# 8x8_LED_Cathode_Base_V5.net
KiCad netlist of a schematic drawn in EAGLE
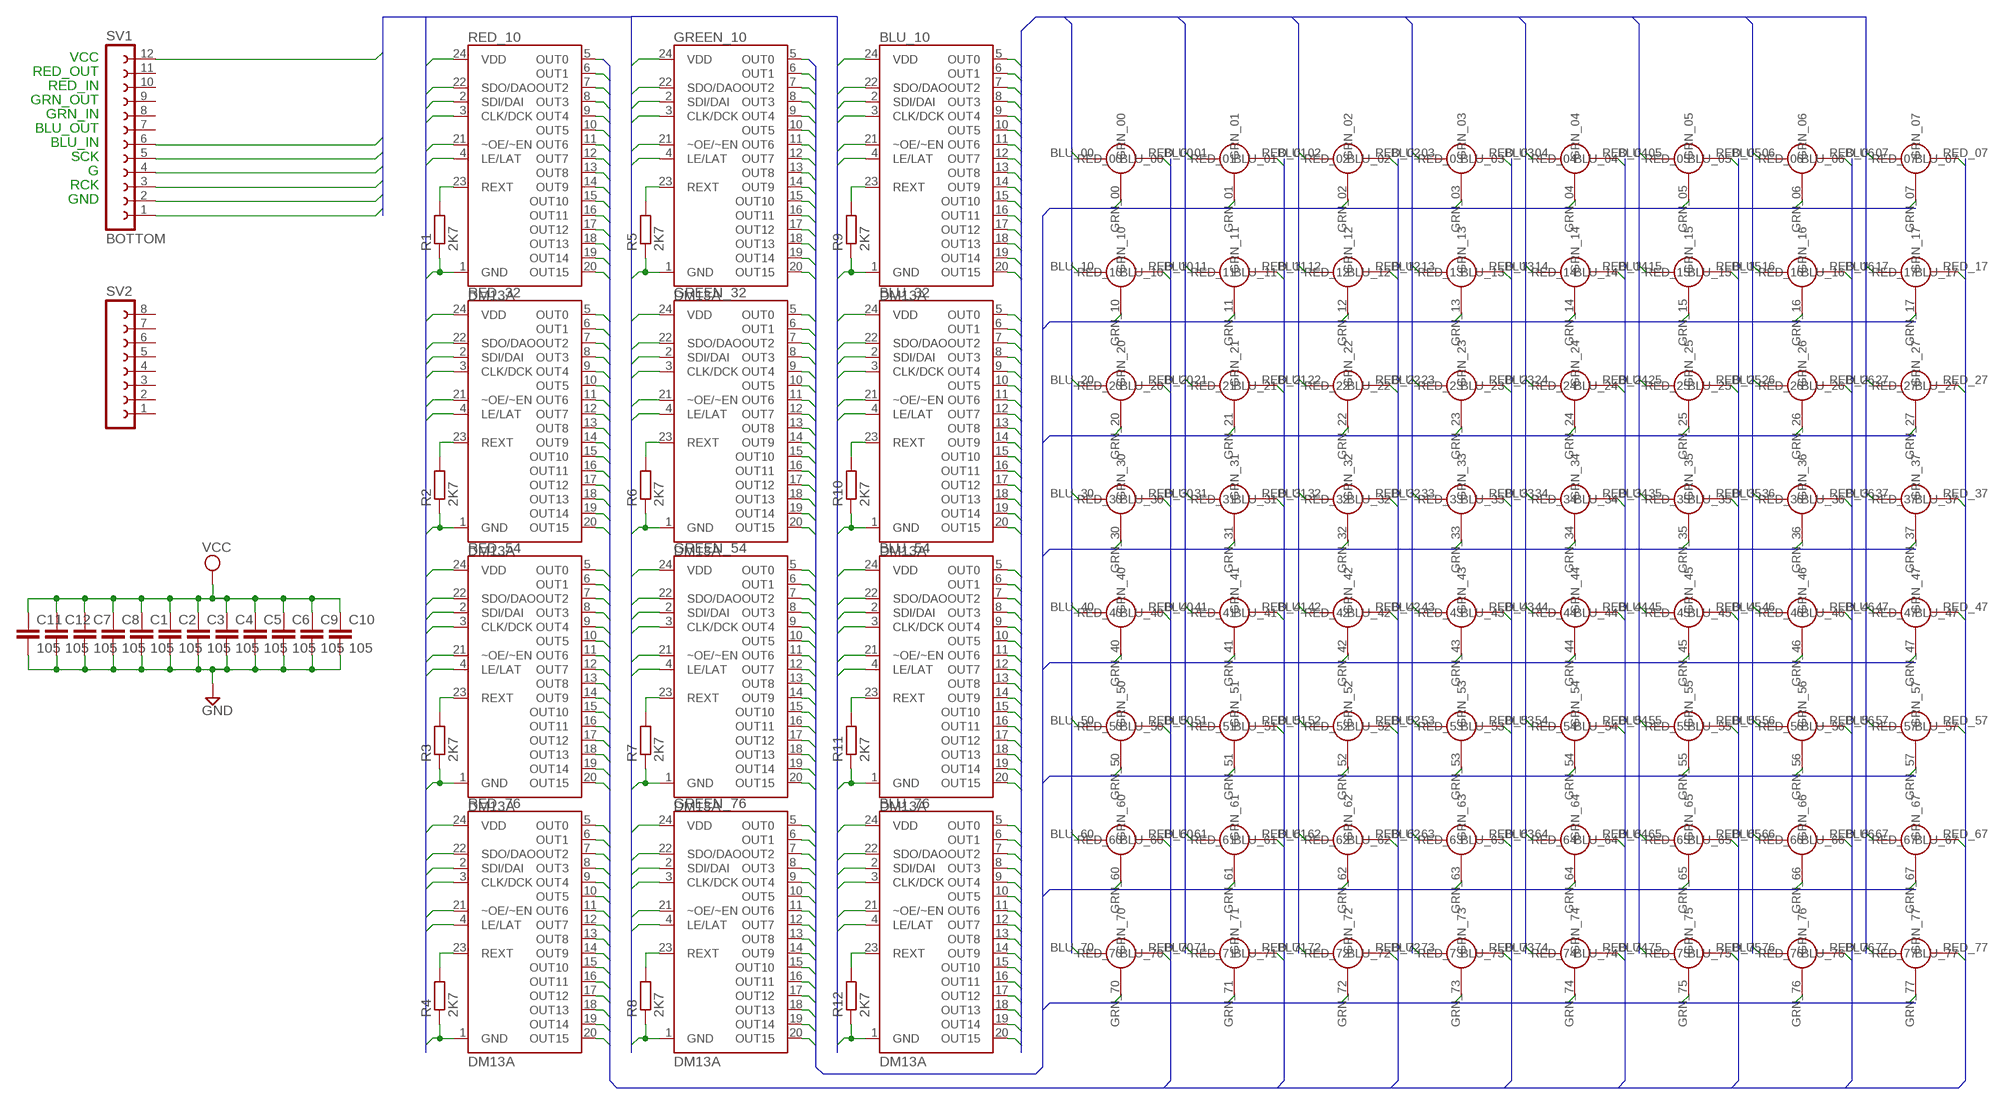
[diagram p0: schematic, sheet 1]

(export (version "E")
  (design (tool "Eeschema 10.0.6"))
  (components
    (comp (ref "BLU_10")
      (value "DM13A")
      (footprint "eagle-import:DIL24-3")
      (libsource (lib "eagle-import") (part "DM13A"))
    )
    (comp (ref "BLU_32")
      (value "DM13A")
      (footprint "eagle-import:DIL24-3")
      (libsource (lib "eagle-import") (part "DM13A"))
    )
    (comp (ref "BLU_54")
      (value "DM13A")
      (footprint "eagle-import:DIL24-3")
      (libsource (lib "eagle-import") (part "DM13A"))
    )
    (comp (ref "BLU_76")
      (value "DM13A")
      (footprint "eagle-import:DIL24-3")
      (libsource (lib "eagle-import") (part "DM13A"))
    )
    (comp (ref "C1")
      (value "105")
      (footprint "eagle-import:C1206")
      (libsource (lib "eagle-import") (part "C-EUC1206"))
    )
    (comp (ref "C2")
      (value "105")
      (footprint "eagle-import:C1206")
      (libsource (lib "eagle-import") (part "C-EUC1206"))
    )
    (comp (ref "C3")
      (value "105")
      (footprint "eagle-import:C1206")
      (libsource (lib "eagle-import") (part "C-EUC1206"))
    )
    (comp (ref "C4")
      (value "105")
      (footprint "eagle-import:C1206")
      (libsource (lib "eagle-import") (part "C-EUC1206"))
    )
    (comp (ref "C5")
      (value "105")
      (footprint "eagle-import:C1206")
      (libsource (lib "eagle-import") (part "C-EUC1206"))
    )
    (comp (ref "C6")
      (value "105")
      (footprint "eagle-import:C1206")
      (libsource (lib "eagle-import") (part "C-EUC1206"))
    )
    (comp (ref "C7")
      (value "105")
      (footprint "eagle-import:C1206")
      (libsource (lib "eagle-import") (part "C-EUC1206"))
    )
    (comp (ref "C8")
      (value "105")
      (footprint "eagle-import:C1206")
      (libsource (lib "eagle-import") (part "C-EUC1206"))
    )
    (comp (ref "C9")
      (value "105")
      (footprint "eagle-import:C1206")
      (libsource (lib "eagle-import") (part "C-EUC1206"))
    )
    (comp (ref "C10")
      (value "105")
      (footprint "eagle-import:C1206")
      (libsource (lib "eagle-import") (part "C-EUC1206"))
    )
    (comp (ref "C11")
      (value "105")
      (footprint "eagle-import:C1206")
      (libsource (lib "eagle-import") (part "C-EUC1206"))
    )
    (comp (ref "C12")
      (value "105")
      (footprint "eagle-import:C1206")
      (libsource (lib "eagle-import") (part "C-EUC1206"))
    )
    (comp (ref "GREEN_10")
      (value "DM13A")
      (footprint "eagle-import:DIL24-3")
      (libsource (lib "eagle-import") (part "DM13A"))
    )
    (comp (ref "GREEN_32")
      (value "DM13A")
      (footprint "eagle-import:DIL24-3")
      (libsource (lib "eagle-import") (part "DM13A"))
    )
    (comp (ref "GREEN_54")
      (value "DM13A")
      (footprint "eagle-import:DIL24-3")
      (libsource (lib "eagle-import") (part "DM13A"))
    )
    (comp (ref "GREEN_76")
      (value "DM13A")
      (footprint "eagle-import:DIL24-3")
      (libsource (lib "eagle-import") (part "DM13A"))
    )
    (comp (ref "R1")
      (value "2K7")
      (footprint "eagle-import:R1206")
      (libsource (lib "eagle-import") (part "R-EU_R1206"))
    )
    (comp (ref "R2")
      (value "2K7")
      (footprint "eagle-import:R1206")
      (libsource (lib "eagle-import") (part "R-EU_R1206"))
    )
    (comp (ref "R3")
      (value "2K7")
      (footprint "eagle-import:R1206")
      (libsource (lib "eagle-import") (part "R-EU_R1206"))
    )
    (comp (ref "R4")
      (value "2K7")
      (footprint "eagle-import:R1206")
      (libsource (lib "eagle-import") (part "R-EU_R1206"))
    )
    (comp (ref "R5")
      (value "2K7")
      (footprint "eagle-import:R1206")
      (libsource (lib "eagle-import") (part "R-EU_R1206"))
    )
    (comp (ref "R6")
      (value "2K7")
      (footprint "eagle-import:R1206")
      (libsource (lib "eagle-import") (part "R-EU_R1206"))
    )
    (comp (ref "R7")
      (value "2K7")
      (footprint "eagle-import:R1206")
      (libsource (lib "eagle-import") (part "R-EU_R1206"))
    )
    (comp (ref "R8")
      (value "2K7")
      (footprint "eagle-import:R1206")
      (libsource (lib "eagle-import") (part "R-EU_R1206"))
    )
    (comp (ref "R9")
      (value "2K7")
      (footprint "eagle-import:R1206")
      (libsource (lib "eagle-import") (part "R-EU_R1206"))
    )
    (comp (ref "R10")
      (value "2K7")
      (footprint "eagle-import:R1206")
      (libsource (lib "eagle-import") (part "R-EU_R1206"))
    )
    (comp (ref "R11")
      (value "2K7")
      (footprint "eagle-import:R1206")
      (libsource (lib "eagle-import") (part "R-EU_R1206"))
    )
    (comp (ref "R12")
      (value "2K7")
      (footprint "eagle-import:R1206")
      (libsource (lib "eagle-import") (part "R-EU_R1206"))
    )
    (comp (ref "RED_10")
      (value "DM13A")
      (footprint "eagle-import:DIL24-3")
      (libsource (lib "eagle-import") (part "DM13A"))
    )
    (comp (ref "RED_32")
      (value "DM13A")
      (footprint "eagle-import:DIL24-3")
      (libsource (lib "eagle-import") (part "DM13A"))
    )
    (comp (ref "RED_54")
      (value "DM13A")
      (footprint "eagle-import:DIL24-3")
      (libsource (lib "eagle-import") (part "DM13A"))
    )
    (comp (ref "RED_76")
      (value "DM13A")
      (footprint "eagle-import:DIL24-3")
      (libsource (lib "eagle-import") (part "DM13A"))
    )
    (comp (ref "SV1")
      (value "BOTTOM")
      (footprint "eagle-import:FE12")
      (libsource (lib "eagle-import") (part "FE12-1"))
    )
    (comp (ref "SV2")
      (value "FE08-1")
      (footprint "eagle-import:FE08")
      (libsource (lib "eagle-import") (part "FE08-1"))
    )
    (comp (ref "U$1")
      (value "8X8_RGB_COLUMN")
      (footprint "eagle-import:8X8_RGB_LED_120")
      (libsource (lib "eagle-import") (part "8X8_RGB_COLUMN"))
    )
  )
  (nets
    (net (code "2") (name "/BLANK") (class "Default")
      (node (ref "BLU_10") (pin "21") (pinfunction "~{OE/}EN_21") (pintype "bidirectional"))
      (node (ref "BLU_32") (pin "21") (pinfunction "~{OE/}EN_21") (pintype "bidirectional"))
      (node (ref "BLU_54") (pin "21") (pinfunction "~{OE/}EN_21") (pintype "bidirectional"))
      (node (ref "BLU_76") (pin "21") (pinfunction "~{OE/}EN_21") (pintype "bidirectional"))
      (node (ref "GREEN_10") (pin "21") (pinfunction "~{OE/}EN_21") (pintype "bidirectional"))
      (node (ref "GREEN_32") (pin "21") (pinfunction "~{OE/}EN_21") (pintype "bidirectional"))
      (node (ref "GREEN_54") (pin "21") (pinfunction "~{OE/}EN_21") (pintype "bidirectional"))
      (node (ref "GREEN_76") (pin "21") (pinfunction "~{OE/}EN_21") (pintype "bidirectional"))
      (node (ref "RED_10") (pin "21") (pinfunction "~{OE/}EN_21") (pintype "bidirectional"))
      (node (ref "RED_32") (pin "21") (pinfunction "~{OE/}EN_21") (pintype "bidirectional"))
      (node (ref "RED_54") (pin "21") (pinfunction "~{OE/}EN_21") (pintype "bidirectional"))
      (node (ref "RED_76") (pin "21") (pinfunction "~{OE/}EN_21") (pintype "bidirectional"))
      (node (ref "SV1") (pin "4") (pinfunction "4_4") (pintype "passive"))
    )
    (net (code "3") (name "/BLU_00") (class "Default")
      (node (ref "BLU_10") (pin "5") (pinfunction "OUT0_5") (pintype "bidirectional"))
      (node (ref "U$1") (pin "BLU_00") (pinfunction "BLU_00_BLU_00") (pintype "bidirectional"))
    )
    (net (code "4") (name "/BLU_01") (class "Default")
      (node (ref "BLU_10") (pin "6") (pinfunction "OUT1_6") (pintype "bidirectional"))
      (node (ref "U$1") (pin "BLU_01") (pinfunction "BLU_01_BLU_01") (pintype "bidirectional"))
    )
    (net (code "5") (name "/BLU_02") (class "Default")
      (node (ref "BLU_10") (pin "7") (pinfunction "OUT2_7") (pintype "bidirectional"))
      (node (ref "U$1") (pin "BLU_02") (pinfunction "BLU_02_BLU_02") (pintype "bidirectional"))
    )
    (net (code "6") (name "/BLU_03") (class "Default")
      (node (ref "BLU_10") (pin "8") (pinfunction "OUT3_8") (pintype "bidirectional"))
      (node (ref "U$1") (pin "BLU_03") (pinfunction "BLU_03_BLU_03") (pintype "bidirectional"))
    )
    (net (code "7") (name "/BLU_04") (class "Default")
      (node (ref "BLU_10") (pin "9") (pinfunction "OUT4_9") (pintype "bidirectional"))
      (node (ref "U$1") (pin "BLU_04") (pinfunction "BLU_04_BLU_04") (pintype "bidirectional"))
    )
    (net (code "8") (name "/BLU_05") (class "Default")
      (node (ref "BLU_10") (pin "10") (pinfunction "OUT5_10") (pintype "bidirectional"))
      (node (ref "U$1") (pin "BLU_05") (pinfunction "BLU_05_BLU_05") (pintype "bidirectional"))
    )
    (net (code "9") (name "/BLU_06") (class "Default")
      (node (ref "BLU_10") (pin "11") (pinfunction "OUT6_11") (pintype "bidirectional"))
      (node (ref "U$1") (pin "BLU_06") (pinfunction "BLU_06_BLU_06") (pintype "bidirectional"))
    )
    (net (code "10") (name "/BLU_07") (class "Default")
      (node (ref "BLU_10") (pin "12") (pinfunction "OUT7_12") (pintype "bidirectional"))
      (node (ref "U$1") (pin "BLU_07") (pinfunction "BLU_07_BLU_07") (pintype "bidirectional"))
    )
    (net (code "11") (name "/BLU_10") (class "Default")
      (node (ref "BLU_10") (pin "13") (pinfunction "OUT8_13") (pintype "bidirectional"))
      (node (ref "U$1") (pin "BLU_10") (pinfunction "BLU_10_BLU_10") (pintype "bidirectional"))
    )
    (net (code "12") (name "/BLU_11") (class "Default")
      (node (ref "BLU_10") (pin "14") (pinfunction "OUT9_14") (pintype "bidirectional"))
      (node (ref "U$1") (pin "BLU_11") (pinfunction "BLU_11_BLU_11") (pintype "bidirectional"))
    )
    (net (code "13") (name "/BLU_12") (class "Default")
      (node (ref "BLU_10") (pin "15") (pinfunction "OUT10_15") (pintype "bidirectional"))
      (node (ref "U$1") (pin "BLU_12") (pinfunction "BLU_12_BLU_12") (pintype "bidirectional"))
    )
    (net (code "14") (name "/BLU_13") (class "Default")
      (node (ref "BLU_10") (pin "16") (pinfunction "OUT11_16") (pintype "bidirectional"))
      (node (ref "U$1") (pin "BLU_13") (pinfunction "BLU_13_BLU_13") (pintype "bidirectional"))
    )
    (net (code "15") (name "/BLU_14") (class "Default")
      (node (ref "BLU_10") (pin "17") (pinfunction "OUT12_17") (pintype "bidirectional"))
      (node (ref "U$1") (pin "BLU_14") (pinfunction "BLU_14_BLU_14") (pintype "bidirectional"))
    )
    (net (code "16") (name "/BLU_15") (class "Default")
      (node (ref "BLU_10") (pin "18") (pinfunction "OUT13_18") (pintype "bidirectional"))
      (node (ref "U$1") (pin "BLU_15") (pinfunction "BLU_15_BLU_15") (pintype "bidirectional"))
    )
    (net (code "17") (name "/BLU_16") (class "Default")
      (node (ref "BLU_10") (pin "19") (pinfunction "OUT14_19") (pintype "bidirectional"))
      (node (ref "U$1") (pin "BLU_16") (pinfunction "BLU_16_BLU_16") (pintype "bidirectional"))
    )
    (net (code "18") (name "/BLU_17") (class "Default")
      (node (ref "BLU_10") (pin "20") (pinfunction "OUT15_20") (pintype "bidirectional"))
      (node (ref "U$1") (pin "BLU_17") (pinfunction "BLU_17_BLU_17") (pintype "bidirectional"))
    )
    (net (code "19") (name "/BLU_20") (class "Default")
      (node (ref "BLU_32") (pin "5") (pinfunction "OUT0_5") (pintype "bidirectional"))
      (node (ref "U$1") (pin "BLU_20") (pinfunction "BLU_20_BLU_20") (pintype "bidirectional"))
    )
    (net (code "20") (name "/BLU_21") (class "Default")
      (node (ref "BLU_32") (pin "6") (pinfunction "OUT1_6") (pintype "bidirectional"))
      (node (ref "U$1") (pin "BLU_21") (pinfunction "BLU_21_BLU_21") (pintype "bidirectional"))
    )
    (net (code "21") (name "/BLU_22") (class "Default")
      (node (ref "BLU_32") (pin "7") (pinfunction "OUT2_7") (pintype "bidirectional"))
      (node (ref "U$1") (pin "BLU_22") (pinfunction "BLU_22_BLU_22") (pintype "bidirectional"))
    )
    (net (code "22") (name "/BLU_23") (class "Default")
      (node (ref "BLU_32") (pin "8") (pinfunction "OUT3_8") (pintype "bidirectional"))
      (node (ref "U$1") (pin "BLU_23") (pinfunction "BLU_23_BLU_23") (pintype "bidirectional"))
    )
    (net (code "23") (name "/BLU_24") (class "Default")
      (node (ref "BLU_32") (pin "9") (pinfunction "OUT4_9") (pintype "bidirectional"))
      (node (ref "U$1") (pin "BLU_24") (pinfunction "BLU_24_BLU_24") (pintype "bidirectional"))
    )
    (net (code "24") (name "/BLU_25") (class "Default")
      (node (ref "BLU_32") (pin "10") (pinfunction "OUT5_10") (pintype "bidirectional"))
      (node (ref "U$1") (pin "BLU_25") (pinfunction "BLU_25_BLU_25") (pintype "bidirectional"))
    )
    (net (code "25") (name "/BLU_26") (class "Default")
      (node (ref "BLU_32") (pin "11") (pinfunction "OUT6_11") (pintype "bidirectional"))
      (node (ref "U$1") (pin "BLU_26") (pinfunction "BLU_26_BLU_26") (pintype "bidirectional"))
    )
    (net (code "26") (name "/BLU_27") (class "Default")
      (node (ref "BLU_32") (pin "12") (pinfunction "OUT7_12") (pintype "bidirectional"))
      (node (ref "U$1") (pin "BLU_27") (pinfunction "BLU_27_BLU_27") (pintype "bidirectional"))
    )
    (net (code "27") (name "/BLU_30") (class "Default")
      (node (ref "BLU_32") (pin "13") (pinfunction "OUT8_13") (pintype "bidirectional"))
      (node (ref "U$1") (pin "BLU_30") (pinfunction "BLU_30_BLU_30") (pintype "bidirectional"))
    )
    (net (code "28") (name "/BLU_31") (class "Default")
      (node (ref "BLU_32") (pin "14") (pinfunction "OUT9_14") (pintype "bidirectional"))
      (node (ref "U$1") (pin "BLU_31") (pinfunction "BLU_31_BLU_31") (pintype "bidirectional"))
    )
    (net (code "29") (name "/BLU_32") (class "Default")
      (node (ref "BLU_32") (pin "15") (pinfunction "OUT10_15") (pintype "bidirectional"))
      (node (ref "U$1") (pin "BLU_32") (pinfunction "BLU_32_BLU_32") (pintype "bidirectional"))
    )
    (net (code "30") (name "/BLU_32_DATA") (class "Default")
      (node (ref "BLU_10") (pin "22") (pinfunction "SDO/DAO_22") (pintype "bidirectional"))
      (node (ref "BLU_32") (pin "2") (pinfunction "SDI/DAI_2") (pintype "bidirectional"))
    )
    (net (code "31") (name "/BLU_33") (class "Default")
      (node (ref "BLU_32") (pin "16") (pinfunction "OUT11_16") (pintype "bidirectional"))
      (node (ref "U$1") (pin "BLU_33") (pinfunction "BLU_33_BLU_33") (pintype "bidirectional"))
    )
    (net (code "32") (name "/BLU_34") (class "Default")
      (node (ref "BLU_32") (pin "17") (pinfunction "OUT12_17") (pintype "bidirectional"))
      (node (ref "U$1") (pin "BLU_34") (pinfunction "BLU_34_BLU_34") (pintype "bidirectional"))
    )
    (net (code "33") (name "/BLU_35") (class "Default")
      (node (ref "BLU_32") (pin "18") (pinfunction "OUT13_18") (pintype "bidirectional"))
      (node (ref "U$1") (pin "BLU_35") (pinfunction "BLU_35_BLU_35") (pintype "bidirectional"))
    )
    (net (code "34") (name "/BLU_36") (class "Default")
      (node (ref "BLU_32") (pin "19") (pinfunction "OUT14_19") (pintype "bidirectional"))
      (node (ref "U$1") (pin "BLU_36") (pinfunction "BLU_36_BLU_36") (pintype "bidirectional"))
    )
    (net (code "35") (name "/BLU_37") (class "Default")
      (node (ref "BLU_32") (pin "20") (pinfunction "OUT15_20") (pintype "bidirectional"))
      (node (ref "U$1") (pin "BLU_37") (pinfunction "BLU_37_BLU_37") (pintype "bidirectional"))
    )
    (net (code "36") (name "/BLU_40") (class "Default")
      (node (ref "BLU_54") (pin "5") (pinfunction "OUT0_5") (pintype "bidirectional"))
      (node (ref "U$1") (pin "BLU_40") (pinfunction "BLU_40_BLU_40") (pintype "bidirectional"))
    )
    (net (code "37") (name "/BLU_41") (class "Default")
      (node (ref "BLU_54") (pin "6") (pinfunction "OUT1_6") (pintype "bidirectional"))
      (node (ref "U$1") (pin "BLU_41") (pinfunction "BLU_41_BLU_41") (pintype "bidirectional"))
    )
    (net (code "38") (name "/BLU_42") (class "Default")
      (node (ref "BLU_54") (pin "7") (pinfunction "OUT2_7") (pintype "bidirectional"))
      (node (ref "U$1") (pin "BLU_42") (pinfunction "BLU_42_BLU_42") (pintype "bidirectional"))
    )
    (net (code "39") (name "/BLU_43") (class "Default")
      (node (ref "BLU_54") (pin "8") (pinfunction "OUT3_8") (pintype "bidirectional"))
      (node (ref "U$1") (pin "BLU_43") (pinfunction "BLU_43_BLU_43") (pintype "bidirectional"))
    )
    (net (code "40") (name "/BLU_44") (class "Default")
      (node (ref "BLU_54") (pin "9") (pinfunction "OUT4_9") (pintype "bidirectional"))
      (node (ref "U$1") (pin "BLU_44") (pinfunction "BLU_44_BLU_44") (pintype "bidirectional"))
    )
    (net (code "41") (name "/BLU_45") (class "Default")
      (node (ref "BLU_54") (pin "10") (pinfunction "OUT5_10") (pintype "bidirectional"))
      (node (ref "U$1") (pin "BLU_45") (pinfunction "BLU_45_BLU_45") (pintype "bidirectional"))
    )
    (net (code "42") (name "/BLU_46") (class "Default")
      (node (ref "BLU_54") (pin "11") (pinfunction "OUT6_11") (pintype "bidirectional"))
      (node (ref "U$1") (pin "BLU_46") (pinfunction "BLU_46_BLU_46") (pintype "bidirectional"))
    )
    (net (code "43") (name "/BLU_47") (class "Default")
      (node (ref "BLU_54") (pin "12") (pinfunction "OUT7_12") (pintype "bidirectional"))
      (node (ref "U$1") (pin "BLU_47") (pinfunction "BLU_47_BLU_47") (pintype "bidirectional"))
    )
    (net (code "44") (name "/BLU_50") (class "Default")
      (node (ref "BLU_54") (pin "13") (pinfunction "OUT8_13") (pintype "bidirectional"))
      (node (ref "U$1") (pin "BLU_50") (pinfunction "BLU_50_BLU_50") (pintype "bidirectional"))
    )
    (net (code "45") (name "/BLU_51") (class "Default")
      (node (ref "BLU_54") (pin "14") (pinfunction "OUT9_14") (pintype "bidirectional"))
      (node (ref "U$1") (pin "BLU_51") (pinfunction "BLU_51_BLU_51") (pintype "bidirectional"))
    )
    (net (code "46") (name "/BLU_52") (class "Default")
      (node (ref "BLU_54") (pin "15") (pinfunction "OUT10_15") (pintype "bidirectional"))
      (node (ref "U$1") (pin "BLU_52") (pinfunction "BLU_52_BLU_52") (pintype "bidirectional"))
    )
    (net (code "47") (name "/BLU_53") (class "Default")
      (node (ref "BLU_54") (pin "16") (pinfunction "OUT11_16") (pintype "bidirectional"))
      (node (ref "U$1") (pin "BLU_53") (pinfunction "BLU_53_BLU_53") (pintype "bidirectional"))
    )
    (net (code "48") (name "/BLU_54") (class "Default")
      (node (ref "BLU_54") (pin "17") (pinfunction "OUT12_17") (pintype "bidirectional"))
      (node (ref "U$1") (pin "BLU_54") (pinfunction "BLU_54_BLU_54") (pintype "bidirectional"))
    )
    (net (code "49") (name "/BLU_54_DATA") (class "Default")
      (node (ref "BLU_32") (pin "22") (pinfunction "SDO/DAO_22") (pintype "bidirectional"))
      (node (ref "BLU_54") (pin "2") (pinfunction "SDI/DAI_2") (pintype "bidirectional"))
    )
    (net (code "50") (name "/BLU_55") (class "Default")
      (node (ref "BLU_54") (pin "18") (pinfunction "OUT13_18") (pintype "bidirectional"))
      (node (ref "U$1") (pin "BLU_55") (pinfunction "BLU_55_BLU_55") (pintype "bidirectional"))
    )
    (net (code "51") (name "/BLU_56") (class "Default")
      (node (ref "BLU_54") (pin "19") (pinfunction "OUT14_19") (pintype "bidirectional"))
      (node (ref "U$1") (pin "BLU_56") (pinfunction "BLU_56_BLU_56") (pintype "bidirectional"))
    )
    (net (code "52") (name "/BLU_57") (class "Default")
      (node (ref "BLU_54") (pin "20") (pinfunction "OUT15_20") (pintype "bidirectional"))
      (node (ref "U$1") (pin "BLU_57") (pinfunction "BLU_57_BLU_57") (pintype "bidirectional"))
    )
    (net (code "53") (name "/BLU_60") (class "Default")
      (node (ref "BLU_76") (pin "5") (pinfunction "OUT0_5") (pintype "bidirectional"))
      (node (ref "U$1") (pin "BLU_60") (pinfunction "BLU_60_BLU_60") (pintype "bidirectional"))
    )
    (net (code "54") (name "/BLU_61") (class "Default")
      (node (ref "BLU_76") (pin "6") (pinfunction "OUT1_6") (pintype "bidirectional"))
      (node (ref "U$1") (pin "BLU_61") (pinfunction "BLU_61_BLU_61") (pintype "bidirectional"))
    )
    (net (code "55") (name "/BLU_62") (class "Default")
      (node (ref "BLU_76") (pin "7") (pinfunction "OUT2_7") (pintype "bidirectional"))
      (node (ref "U$1") (pin "BLU_62") (pinfunction "BLU_62_BLU_62") (pintype "bidirectional"))
    )
    (net (code "56") (name "/BLU_63") (class "Default")
      (node (ref "BLU_76") (pin "8") (pinfunction "OUT3_8") (pintype "bidirectional"))
      (node (ref "U$1") (pin "BLU_63") (pinfunction "BLU_63_BLU_63") (pintype "bidirectional"))
    )
    (net (code "57") (name "/BLU_64") (class "Default")
      (node (ref "BLU_76") (pin "9") (pinfunction "OUT4_9") (pintype "bidirectional"))
      (node (ref "U$1") (pin "BLU_64") (pinfunction "BLU_64_BLU_64") (pintype "bidirectional"))
    )
    (net (code "58") (name "/BLU_65") (class "Default")
      (node (ref "BLU_76") (pin "10") (pinfunction "OUT5_10") (pintype "bidirectional"))
      (node (ref "U$1") (pin "BLU_65") (pinfunction "BLU_65_BLU_65") (pintype "bidirectional"))
    )
    (net (code "59") (name "/BLU_66") (class "Default")
      (node (ref "BLU_76") (pin "11") (pinfunction "OUT6_11") (pintype "bidirectional"))
      (node (ref "U$1") (pin "BLU_66") (pinfunction "BLU_66_BLU_66") (pintype "bidirectional"))
    )
    (net (code "60") (name "/BLU_67") (class "Default")
      (node (ref "BLU_76") (pin "12") (pinfunction "OUT7_12") (pintype "bidirectional"))
      (node (ref "U$1") (pin "BLU_67") (pinfunction "BLU_67_BLU_67") (pintype "bidirectional"))
    )
    (net (code "61") (name "/BLU_70") (class "Default")
      (node (ref "BLU_76") (pin "13") (pinfunction "OUT8_13") (pintype "bidirectional"))
      (node (ref "U$1") (pin "BLU_70") (pinfunction "BLU_70_BLU_70") (pintype "bidirectional"))
    )
    (net (code "62") (name "/BLU_71") (class "Default")
      (node (ref "BLU_76") (pin "14") (pinfunction "OUT9_14") (pintype "bidirectional"))
      (node (ref "U$1") (pin "BLU_71") (pinfunction "BLU_71_BLU_71") (pintype "bidirectional"))
    )
    (net (code "63") (name "/BLU_72") (class "Default")
      (node (ref "BLU_76") (pin "15") (pinfunction "OUT10_15") (pintype "bidirectional"))
      (node (ref "U$1") (pin "BLU_72") (pinfunction "BLU_72_BLU_72") (pintype "bidirectional"))
    )
    (net (code "64") (name "/BLU_73") (class "Default")
      (node (ref "BLU_76") (pin "16") (pinfunction "OUT11_16") (pintype "bidirectional"))
      (node (ref "U$1") (pin "BLU_73") (pinfunction "BLU_73_BLU_73") (pintype "bidirectional"))
    )
    (net (code "65") (name "/BLU_74") (class "Default")
      (node (ref "BLU_76") (pin "17") (pinfunction "OUT12_17") (pintype "bidirectional"))
      (node (ref "U$1") (pin "BLU_74") (pinfunction "BLU_74_BLU_74") (pintype "bidirectional"))
    )
    (net (code "66") (name "/BLU_75") (class "Default")
      (node (ref "BLU_76") (pin "18") (pinfunction "OUT13_18") (pintype "bidirectional"))
      (node (ref "U$1") (pin "BLU_75") (pinfunction "BLU_75_BLU_75") (pintype "bidirectional"))
    )
    (net (code "67") (name "/BLU_76") (class "Default")
      (node (ref "BLU_76") (pin "19") (pinfunction "OUT14_19") (pintype "bidirectional"))
      (node (ref "U$1") (pin "BLU_76") (pinfunction "BLU_76_BLU_76") (pintype "bidirectional"))
    )
    (net (code "68") (name "/BLU_76_DATA") (class "Default")
      (node (ref "BLU_54") (pin "22") (pinfunction "SDO/DAO_22") (pintype "bidirectional"))
      (node (ref "BLU_76") (pin "2") (pinfunction "SDI/DAI_2") (pintype "bidirectional"))
    )
    (net (code "69") (name "/BLU_77") (class "Default")
      (node (ref "BLU_76") (pin "20") (pinfunction "OUT15_20") (pintype "bidirectional"))
      (node (ref "U$1") (pin "BLU_77") (pinfunction "BLU_77_BLU_77") (pintype "bidirectional"))
    )
    (net (code "70") (name "/BLU_IN") (class "Default")
      (node (ref "BLU_10") (pin "2") (pinfunction "SDI/DAI_2") (pintype "bidirectional"))
      (node (ref "SV1") (pin "6") (pinfunction "6_6") (pintype "passive"))
    )
    (net (code "71") (name "/BLU_OUT") (class "Default")
      (node (ref "BLU_76") (pin "22") (pinfunction "SDO/DAO_22") (pintype "bidirectional"))
      (node (ref "GREEN_10") (pin "2") (pinfunction "SDI/DAI_2") (pintype "bidirectional"))
    )
    (net (code "72") (name "/CLOCK") (class "Default")
      (node (ref "BLU_10") (pin "3") (pinfunction "CLK/DCK_3") (pintype "bidirectional"))
      (node (ref "BLU_32") (pin "3") (pinfunction "CLK/DCK_3") (pintype "bidirectional"))
      (node (ref "BLU_54") (pin "3") (pinfunction "CLK/DCK_3") (pintype "bidirectional"))
      (node (ref "BLU_76") (pin "3") (pinfunction "CLK/DCK_3") (pintype "bidirectional"))
      (node (ref "GREEN_10") (pin "3") (pinfunction "CLK/DCK_3") (pintype "bidirectional"))
      (node (ref "GREEN_32") (pin "3") (pinfunction "CLK/DCK_3") (pintype "bidirectional"))
      (node (ref "GREEN_54") (pin "3") (pinfunction "CLK/DCK_3") (pintype "bidirectional"))
      (node (ref "GREEN_76") (pin "3") (pinfunction "CLK/DCK_3") (pintype "bidirectional"))
      (node (ref "RED_10") (pin "3") (pinfunction "CLK/DCK_3") (pintype "bidirectional"))
      (node (ref "RED_32") (pin "3") (pinfunction "CLK/DCK_3") (pintype "bidirectional"))
      (node (ref "RED_54") (pin "3") (pinfunction "CLK/DCK_3") (pintype "bidirectional"))
      (node (ref "RED_76") (pin "3") (pinfunction "CLK/DCK_3") (pintype "bidirectional"))
      (node (ref "SV1") (pin "5") (pinfunction "5_5") (pintype "passive"))
    )
    (net (code "73") (name "/GRN_00") (class "Default")
      (node (ref "GREEN_10") (pin "5") (pinfunction "OUT0_5") (pintype "bidirectional"))
      (node (ref "U$1") (pin "GRN_00") (pinfunction "GRN_00_GRN_00") (pintype "bidirectional"))
    )
    (net (code "74") (name "/GRN_01") (class "Default")
      (node (ref "GREEN_10") (pin "6") (pinfunction "OUT1_6") (pintype "bidirectional"))
      (node (ref "U$1") (pin "GRN_01") (pinfunction "GRN_01_GRN_01") (pintype "bidirectional"))
    )
    (net (code "75") (name "/GRN_02") (class "Default")
      (node (ref "GREEN_10") (pin "7") (pinfunction "OUT2_7") (pintype "bidirectional"))
      (node (ref "U$1") (pin "GRN_02") (pinfunction "GRN_02_GRN_02") (pintype "bidirectional"))
    )
    (net (code "76") (name "/GRN_03") (class "Default")
      (node (ref "GREEN_10") (pin "8") (pinfunction "OUT3_8") (pintype "bidirectional"))
      (node (ref "U$1") (pin "GRN_03") (pinfunction "GRN_03_GRN_03") (pintype "bidirectional"))
    )
    (net (code "77") (name "/GRN_04") (class "Default")
      (node (ref "GREEN_10") (pin "9") (pinfunction "OUT4_9") (pintype "bidirectional"))
      (node (ref "U$1") (pin "GRN_04") (pinfunction "GRN_04_GRN_04") (pintype "bidirectional"))
    )
    (net (code "78") (name "/GRN_05") (class "Default")
      (node (ref "GREEN_10") (pin "10") (pinfunction "OUT5_10") (pintype "bidirectional"))
      (node (ref "U$1") (pin "GRN_05") (pinfunction "GRN_05_GRN_05") (pintype "bidirectional"))
    )
    (net (code "79") (name "/GRN_06") (class "Default")
      (node (ref "GREEN_10") (pin "11") (pinfunction "OUT6_11") (pintype "bidirectional"))
      (node (ref "U$1") (pin "GRN_06") (pinfunction "GRN_06_GRN_06") (pintype "bidirectional"))
    )
    (net (code "80") (name "/GRN_07") (class "Default")
      (node (ref "GREEN_10") (pin "12") (pinfunction "OUT7_12") (pintype "bidirectional"))
      (node (ref "U$1") (pin "GRN_07") (pinfunction "GRN_07_GRN_07") (pintype "bidirectional"))
    )
    (net (code "81") (name "/GRN_10") (class "Default")
      (node (ref "GREEN_10") (pin "13") (pinfunction "OUT8_13") (pintype "bidirectional"))
      (node (ref "U$1") (pin "GRN_10") (pinfunction "GRN_10_GRN_10") (pintype "bidirectional"))
    )
    (net (code "82") (name "/GRN_11") (class "Default")
      (node (ref "GREEN_10") (pin "14") (pinfunction "OUT9_14") (pintype "bidirectional"))
      (node (ref "U$1") (pin "GRN_11") (pinfunction "GRN_11_GRN_11") (pintype "bidirectional"))
    )
    (net (code "83") (name "/GRN_12") (class "Default")
      (node (ref "GREEN_10") (pin "15") (pinfunction "OUT10_15") (pintype "bidirectional"))
      (node (ref "U$1") (pin "GRN_12") (pinfunction "GRN_12_GRN_12") (pintype "bidirectional"))
    )
    (net (code "84") (name "/GRN_13") (class "Default")
      (node (ref "GREEN_10") (pin "16") (pinfunction "OUT11_16") (pintype "bidirectional"))
      (node (ref "U$1") (pin "GRN_13") (pinfunction "GRN_13_GRN_13") (pintype "bidirectional"))
    )
    (net (code "85") (name "/GRN_14") (class "Default")
      (node (ref "GREEN_10") (pin "17") (pinfunction "OUT12_17") (pintype "bidirectional"))
      (node (ref "U$1") (pin "GRN_14") (pinfunction "GRN_14_GRN_14") (pintype "bidirectional"))
    )
    (net (code "86") (name "/GRN_15") (class "Default")
      (node (ref "GREEN_10") (pin "18") (pinfunction "OUT13_18") (pintype "bidirectional"))
      (node (ref "U$1") (pin "GRN_15") (pinfunction "GRN_15_GRN_15") (pintype "bidirectional"))
    )
    (net (code "87") (name "/GRN_16") (class "Default")
      (node (ref "GREEN_10") (pin "19") (pinfunction "OUT14_19") (pintype "bidirectional"))
      (node (ref "U$1") (pin "GRN_16") (pinfunction "GRN_16_GRN_16") (pintype "bidirectional"))
    )
    (net (code "88") (name "/GRN_17") (class "Default")
      (node (ref "GREEN_10") (pin "20") (pinfunction "OUT15_20") (pintype "bidirectional"))
      (node (ref "U$1") (pin "GRN_17") (pinfunction "GRN_17_GRN_17") (pintype "bidirectional"))
    )
    (net (code "89") (name "/GRN_20") (class "Default")
      (node (ref "GREEN_32") (pin "5") (pinfunction "OUT0_5") (pintype "bidirectional"))
      (node (ref "U$1") (pin "GRN_20") (pinfunction "GRN_20_GRN_20") (pintype "bidirectional"))
    )
    (net (code "90") (name "/GRN_21") (class "Default")
      (node (ref "GREEN_32") (pin "6") (pinfunction "OUT1_6") (pintype "bidirectional"))
      (node (ref "U$1") (pin "GRN_21") (pinfunction "GRN_21_GRN_21") (pintype "bidirectional"))
    )
    (net (code "91") (name "/GRN_22") (class "Default")
      (node (ref "GREEN_32") (pin "7") (pinfunction "OUT2_7") (pintype "bidirectional"))
      (node (ref "U$1") (pin "GRN_22") (pinfunction "GRN_22_GRN_22") (pintype "bidirectional"))
    )
    (net (code "92") (name "/GRN_23") (class "Default")
      (node (ref "GREEN_32") (pin "8") (pinfunction "OUT3_8") (pintype "bidirectional"))
      (node (ref "U$1") (pin "GRN_23") (pinfunction "GRN_23_GRN_23") (pintype "bidirectional"))
    )
    (net (code "93") (name "/GRN_24") (class "Default")
      (node (ref "GREEN_32") (pin "9") (pinfunction "OUT4_9") (pintype "bidirectional"))
      (node (ref "U$1") (pin "GRN_24") (pinfunction "GRN_24_GRN_24") (pintype "bidirectional"))
    )
    (net (code "94") (name "/GRN_25") (class "Default")
      (node (ref "GREEN_32") (pin "10") (pinfunction "OUT5_10") (pintype "bidirectional"))
      (node (ref "U$1") (pin "GRN_25") (pinfunction "GRN_25_GRN_25") (pintype "bidirectional"))
    )
    (net (code "95") (name "/GRN_26") (class "Default")
      (node (ref "GREEN_32") (pin "11") (pinfunction "OUT6_11") (pintype "bidirectional"))
      (node (ref "U$1") (pin "GRN_26") (pinfunction "GRN_26_GRN_26") (pintype "bidirectional"))
    )
    (net (code "96") (name "/GRN_27") (class "Default")
      (node (ref "GREEN_32") (pin "12") (pinfunction "OUT7_12") (pintype "bidirectional"))
      (node (ref "U$1") (pin "GRN_27") (pinfunction "GRN_27_GRN_27") (pintype "bidirectional"))
    )
    (net (code "97") (name "/GRN_30") (class "Default")
      (node (ref "GREEN_32") (pin "13") (pinfunction "OUT8_13") (pintype "bidirectional"))
      (node (ref "U$1") (pin "GRN_30") (pinfunction "GRN_30_GRN_30") (pintype "bidirectional"))
    )
    (net (code "98") (name "/GRN_31") (class "Default")
      (node (ref "GREEN_32") (pin "14") (pinfunction "OUT9_14") (pintype "bidirectional"))
      (node (ref "U$1") (pin "GRN_31") (pinfunction "GRN_31_GRN_31") (pintype "bidirectional"))
    )
    (net (code "99") (name "/GRN_32") (class "Default")
      (node (ref "GREEN_32") (pin "15") (pinfunction "OUT10_15") (pintype "bidirectional"))
      (node (ref "U$1") (pin "GRN_32") (pinfunction "GRN_32_GRN_32") (pintype "bidirectional"))
    )
    (net (code "100") (name "/GRN_32_DATA") (class "Default")
      (node (ref "GREEN_10") (pin "22") (pinfunction "SDO/DAO_22") (pintype "bidirectional"))
      (node (ref "GREEN_32") (pin "2") (pinfunction "SDI/DAI_2") (pintype "bidirectional"))
    )
    (net (code "101") (name "/GRN_33") (class "Default")
      (node (ref "GREEN_32") (pin "16") (pinfunction "OUT11_16") (pintype "bidirectional"))
      (node (ref "U$1") (pin "GRN_33") (pinfunction "GRN_33_GRN_33") (pintype "bidirectional"))
    )
    (net (code "102") (name "/GRN_34") (class "Default")
      (node (ref "GREEN_32") (pin "17") (pinfunction "OUT12_17") (pintype "bidirectional"))
      (node (ref "U$1") (pin "GRN_34") (pinfunction "GRN_34_GRN_34") (pintype "bidirectional"))
    )
    (net (code "103") (name "/GRN_35") (class "Default")
      (node (ref "GREEN_32") (pin "18") (pinfunction "OUT13_18") (pintype "bidirectional"))
      (node (ref "U$1") (pin "GRN_35") (pinfunction "GRN_35_GRN_35") (pintype "bidirectional"))
    )
    (net (code "104") (name "/GRN_36") (class "Default")
      (node (ref "GREEN_32") (pin "19") (pinfunction "OUT14_19") (pintype "bidirectional"))
      (node (ref "U$1") (pin "GRN_36") (pinfunction "GRN_36_GRN_36") (pintype "bidirectional"))
    )
    (net (code "105") (name "/GRN_37") (class "Default")
      (node (ref "GREEN_32") (pin "20") (pinfunction "OUT15_20") (pintype "bidirectional"))
      (node (ref "U$1") (pin "GRN_37") (pinfunction "GRN_37_GRN_37") (pintype "bidirectional"))
    )
    (net (code "106") (name "/GRN_40") (class "Default")
      (node (ref "GREEN_54") (pin "5") (pinfunction "OUT0_5") (pintype "bidirectional"))
      (node (ref "U$1") (pin "GRN_40") (pinfunction "GRN_40_GRN_40") (pintype "bidirectional"))
    )
    (net (code "107") (name "/GRN_41") (class "Default")
      (node (ref "GREEN_54") (pin "6") (pinfunction "OUT1_6") (pintype "bidirectional"))
      (node (ref "U$1") (pin "GRN_41") (pinfunction "GRN_41_GRN_41") (pintype "bidirectional"))
    )
    (net (code "108") (name "/GRN_42") (class "Default")
      (node (ref "GREEN_54") (pin "7") (pinfunction "OUT2_7") (pintype "bidirectional"))
      (node (ref "U$1") (pin "GRN_42") (pinfunction "GRN_42_GRN_42") (pintype "bidirectional"))
    )
    (net (code "109") (name "/GRN_43") (class "Default")
      (node (ref "GREEN_54") (pin "8") (pinfunction "OUT3_8") (pintype "bidirectional"))
      (node (ref "U$1") (pin "GRN_43") (pinfunction "GRN_43_GRN_43") (pintype "bidirectional"))
    )
    (net (code "110") (name "/GRN_44") (class "Default")
      (node (ref "GREEN_54") (pin "9") (pinfunction "OUT4_9") (pintype "bidirectional"))
      (node (ref "U$1") (pin "GRN_44") (pinfunction "GRN_44_GRN_44") (pintype "bidirectional"))
    )
    (net (code "111") (name "/GRN_45") (class "Default")
      (node (ref "GREEN_54") (pin "10") (pinfunction "OUT5_10") (pintype "bidirectional"))
      (node (ref "U$1") (pin "GRN_45") (pinfunction "GRN_45_GRN_45") (pintype "bidirectional"))
    )
    (net (code "112") (name "/GRN_46") (class "Default")
      (node (ref "GREEN_54") (pin "11") (pinfunction "OUT6_11") (pintype "bidirectional"))
      (node (ref "U$1") (pin "GRN_46") (pinfunction "GRN_46_GRN_46") (pintype "bidirectional"))
    )
    (net (code "113") (name "/GRN_47") (class "Default")
      (node (ref "GREEN_54") (pin "12") (pinfunction "OUT7_12") (pintype "bidirectional"))
      (node (ref "U$1") (pin "GRN_47") (pinfunction "GRN_47_GRN_47") (pintype "bidirectional"))
    )
    (net (code "114") (name "/GRN_50") (class "Default")
      (node (ref "GREEN_54") (pin "13") (pinfunction "OUT8_13") (pintype "bidirectional"))
      (node (ref "U$1") (pin "GRN_50") (pinfunction "GRN_50_GRN_50") (pintype "bidirectional"))
    )
    (net (code "115") (name "/GRN_51") (class "Default")
      (node (ref "GREEN_54") (pin "14") (pinfunction "OUT9_14") (pintype "bidirectional"))
      (node (ref "U$1") (pin "GRN_51") (pinfunction "GRN_51_GRN_51") (pintype "bidirectional"))
    )
    (net (code "116") (name "/GRN_52") (class "Default")
      (node (ref "GREEN_54") (pin "15") (pinfunction "OUT10_15") (pintype "bidirectional"))
      (node (ref "U$1") (pin "GRN_52") (pinfunction "GRN_52_GRN_52") (pintype "bidirectional"))
    )
    (net (code "117") (name "/GRN_53") (class "Default")
      (node (ref "GREEN_54") (pin "16") (pinfunction "OUT11_16") (pintype "bidirectional"))
      (node (ref "U$1") (pin "GRN_53") (pinfunction "GRN_53_GRN_53") (pintype "bidirectional"))
    )
    (net (code "118") (name "/GRN_54") (class "Default")
      (node (ref "GREEN_54") (pin "17") (pinfunction "OUT12_17") (pintype "bidirectional"))
      (node (ref "U$1") (pin "GRN_54") (pinfunction "GRN_54_GRN_54") (pintype "bidirectional"))
    )
    (net (code "119") (name "/GRN_54_DATA") (class "Default")
      (node (ref "GREEN_32") (pin "22") (pinfunction "SDO/DAO_22") (pintype "bidirectional"))
      (node (ref "GREEN_54") (pin "2") (pinfunction "SDI/DAI_2") (pintype "bidirectional"))
    )
    (net (code "120") (name "/GRN_55") (class "Default")
      (node (ref "GREEN_54") (pin "18") (pinfunction "OUT13_18") (pintype "bidirectional"))
      (node (ref "U$1") (pin "GRN_55") (pinfunction "GRN_55_GRN_55") (pintype "bidirectional"))
    )
    (net (code "121") (name "/GRN_56") (class "Default")
      (node (ref "GREEN_54") (pin "19") (pinfunction "OUT14_19") (pintype "bidirectional"))
      (node (ref "U$1") (pin "GRN_56") (pinfunction "GRN_56_GRN_56") (pintype "bidirectional"))
    )
    (net (code "122") (name "/GRN_57") (class "Default")
      (node (ref "GREEN_54") (pin "20") (pinfunction "OUT15_20") (pintype "bidirectional"))
      (node (ref "U$1") (pin "GRN_57") (pinfunction "GRN_57_GRN_57") (pintype "bidirectional"))
    )
    (net (code "123") (name "/GRN_60") (class "Default")
      (node (ref "GREEN_76") (pin "5") (pinfunction "OUT0_5") (pintype "bidirectional"))
      (node (ref "U$1") (pin "GRN_60") (pinfunction "GRN_60_GRN_60") (pintype "bidirectional"))
    )
    (net (code "124") (name "/GRN_61") (class "Default")
      (node (ref "GREEN_76") (pin "6") (pinfunction "OUT1_6") (pintype "bidirectional"))
      (node (ref "U$1") (pin "GRN_61") (pinfunction "GRN_61_GRN_61") (pintype "bidirectional"))
    )
    (net (code "125") (name "/GRN_62") (class "Default")
      (node (ref "GREEN_76") (pin "7") (pinfunction "OUT2_7") (pintype "bidirectional"))
      (node (ref "U$1") (pin "GRN_62") (pinfunction "GRN_62_GRN_62") (pintype "bidirectional"))
    )
    (net (code "126") (name "/GRN_63") (class "Default")
      (node (ref "GREEN_76") (pin "8") (pinfunction "OUT3_8") (pintype "bidirectional"))
      (node (ref "U$1") (pin "GRN_63") (pinfunction "GRN_63_GRN_63") (pintype "bidirectional"))
    )
    (net (code "127") (name "/GRN_64") (class "Default")
      (node (ref "GREEN_76") (pin "9") (pinfunction "OUT4_9") (pintype "bidirectional"))
      (node (ref "U$1") (pin "GRN_64") (pinfunction "GRN_64_GRN_64") (pintype "bidirectional"))
    )
    (net (code "128") (name "/GRN_65") (class "Default")
      (node (ref "GREEN_76") (pin "10") (pinfunction "OUT5_10") (pintype "bidirectional"))
      (node (ref "U$1") (pin "GRN_65") (pinfunction "GRN_65_GRN_65") (pintype "bidirectional"))
    )
    (net (code "129") (name "/GRN_66") (class "Default")
      (node (ref "GREEN_76") (pin "11") (pinfunction "OUT6_11") (pintype "bidirectional"))
      (node (ref "U$1") (pin "GRN_66") (pinfunction "GRN_66_GRN_66") (pintype "bidirectional"))
    )
    (net (code "130") (name "/GRN_67") (class "Default")
      (node (ref "GREEN_76") (pin "12") (pinfunction "OUT7_12") (pintype "bidirectional"))
      (node (ref "U$1") (pin "GRN_67") (pinfunction "GRN_67_GRN_67") (pintype "bidirectional"))
    )
    (net (code "131") (name "/GRN_70") (class "Default")
      (node (ref "GREEN_76") (pin "13") (pinfunction "OUT8_13") (pintype "bidirectional"))
      (node (ref "U$1") (pin "GRN_70") (pinfunction "GRN_70_GRN_70") (pintype "bidirectional"))
    )
    (net (code "132") (name "/GRN_71") (class "Default")
      (node (ref "GREEN_76") (pin "14") (pinfunction "OUT9_14") (pintype "bidirectional"))
      (node (ref "U$1") (pin "GRN_71") (pinfunction "GRN_71_GRN_71") (pintype "bidirectional"))
    )
    (net (code "133") (name "/GRN_72") (class "Default")
      (node (ref "GREEN_76") (pin "15") (pinfunction "OUT10_15") (pintype "bidirectional"))
      (node (ref "U$1") (pin "GRN_72") (pinfunction "GRN_72_GRN_72") (pintype "bidirectional"))
    )
    (net (code "134") (name "/GRN_73") (class "Default")
      (node (ref "GREEN_76") (pin "16") (pinfunction "OUT11_16") (pintype "bidirectional"))
      (node (ref "U$1") (pin "GRN_73") (pinfunction "GRN_73_GRN_73") (pintype "bidirectional"))
    )
    (net (code "135") (name "/GRN_74") (class "Default")
      (node (ref "GREEN_76") (pin "17") (pinfunction "OUT12_17") (pintype "bidirectional"))
      (node (ref "U$1") (pin "GRN_74") (pinfunction "GRN_74_GRN_74") (pintype "bidirectional"))
    )
    (net (code "136") (name "/GRN_75") (class "Default")
      (node (ref "GREEN_76") (pin "18") (pinfunction "OUT13_18") (pintype "bidirectional"))
      (node (ref "U$1") (pin "GRN_75") (pinfunction "GRN_75_GRN_75") (pintype "bidirectional"))
    )
    (net (code "137") (name "/GRN_76") (class "Default")
      (node (ref "GREEN_76") (pin "19") (pinfunction "OUT14_19") (pintype "bidirectional"))
      (node (ref "U$1") (pin "GRN_76") (pinfunction "GRN_76_GRN_76") (pintype "bidirectional"))
    )
    (net (code "138") (name "/GRN_76_DATA") (class "Default")
      (node (ref "GREEN_54") (pin "22") (pinfunction "SDO/DAO_22") (pintype "bidirectional"))
      (node (ref "GREEN_76") (pin "2") (pinfunction "SDI/DAI_2") (pintype "bidirectional"))
    )
    (net (code "139") (name "/GRN_77") (class "Default")
      (node (ref "GREEN_76") (pin "20") (pinfunction "OUT15_20") (pintype "bidirectional"))
      (node (ref "U$1") (pin "GRN_77") (pinfunction "GRN_77_GRN_77") (pintype "bidirectional"))
    )
    (net (code "140") (name "/GRN_OUT") (class "Default")
      (node (ref "GREEN_76") (pin "22") (pinfunction "SDO/DAO_22") (pintype "bidirectional"))
      (node (ref "RED_10") (pin "2") (pinfunction "SDI/DAI_2") (pintype "bidirectional"))
    )
    (net (code "141") (name "/LATCH") (class "Default")
      (node (ref "BLU_10") (pin "4") (pinfunction "LE/LAT_4") (pintype "bidirectional"))
      (node (ref "BLU_32") (pin "4") (pinfunction "LE/LAT_4") (pintype "bidirectional"))
      (node (ref "BLU_54") (pin "4") (pinfunction "LE/LAT_4") (pintype "bidirectional"))
      (node (ref "BLU_76") (pin "4") (pinfunction "LE/LAT_4") (pintype "bidirectional"))
      (node (ref "GREEN_10") (pin "4") (pinfunction "LE/LAT_4") (pintype "bidirectional"))
      (node (ref "GREEN_32") (pin "4") (pinfunction "LE/LAT_4") (pintype "bidirectional"))
      (node (ref "GREEN_54") (pin "4") (pinfunction "LE/LAT_4") (pintype "bidirectional"))
      (node (ref "GREEN_76") (pin "4") (pinfunction "LE/LAT_4") (pintype "bidirectional"))
      (node (ref "RED_10") (pin "4") (pinfunction "LE/LAT_4") (pintype "bidirectional"))
      (node (ref "RED_32") (pin "4") (pinfunction "LE/LAT_4") (pintype "bidirectional"))
      (node (ref "RED_54") (pin "4") (pinfunction "LE/LAT_4") (pintype "bidirectional"))
      (node (ref "RED_76") (pin "4") (pinfunction "LE/LAT_4") (pintype "bidirectional"))
      (node (ref "SV1") (pin "3") (pinfunction "3_3") (pintype "passive"))
    )
    (net (code "142") (name "/RED_00") (class "Default")
      (node (ref "RED_10") (pin "5") (pinfunction "OUT0_5") (pintype "bidirectional"))
      (node (ref "U$1") (pin "RED_00") (pinfunction "RED_00_RED_00") (pintype "bidirectional"))
    )
    (net (code "143") (name "/RED_01") (class "Default")
      (node (ref "RED_10") (pin "6") (pinfunction "OUT1_6") (pintype "bidirectional"))
      (node (ref "U$1") (pin "RED_01") (pinfunction "RED_01_RED_01") (pintype "bidirectional"))
    )
    (net (code "144") (name "/RED_02") (class "Default")
      (node (ref "RED_10") (pin "7") (pinfunction "OUT2_7") (pintype "bidirectional"))
      (node (ref "U$1") (pin "RED_02") (pinfunction "RED_02_RED_02") (pintype "bidirectional"))
    )
    (net (code "145") (name "/RED_03") (class "Default")
      (node (ref "RED_10") (pin "8") (pinfunction "OUT3_8") (pintype "bidirectional"))
      (node (ref "U$1") (pin "RED_03") (pinfunction "RED_03_RED_03") (pintype "bidirectional"))
    )
    (net (code "146") (name "/RED_04") (class "Default")
      (node (ref "RED_10") (pin "9") (pinfunction "OUT4_9") (pintype "bidirectional"))
      (node (ref "U$1") (pin "RED_04") (pinfunction "RED_04_RED_04") (pintype "bidirectional"))
    )
    (net (code "147") (name "/RED_05") (class "Default")
      (node (ref "RED_10") (pin "10") (pinfunction "OUT5_10") (pintype "bidirectional"))
      (node (ref "U$1") (pin "RED_05") (pinfunction "RED_05_RED_05") (pintype "bidirectional"))
    )
    (net (code "148") (name "/RED_06") (class "Default")
      (node (ref "RED_10") (pin "11") (pinfunction "OUT6_11") (pintype "bidirectional"))
      (node (ref "U$1") (pin "RED_06") (pinfunction "RED_06_RED_06") (pintype "bidirectional"))
    )
    (net (code "149") (name "/RED_07") (class "Default")
      (node (ref "RED_10") (pin "12") (pinfunction "OUT7_12") (pintype "bidirectional"))
      (node (ref "U$1") (pin "RED_07") (pinfunction "RED_07_RED_07") (pintype "bidirectional"))
    )
    (net (code "150") (name "/RED_10") (class "Default")
      (node (ref "RED_10") (pin "13") (pinfunction "OUT8_13") (pintype "bidirectional"))
      (node (ref "U$1") (pin "RED_10") (pinfunction "RED_10_RED_10") (pintype "bidirectional"))
    )
    (net (code "151") (name "/RED_11") (class "Default")
      (node (ref "RED_10") (pin "14") (pinfunction "OUT9_14") (pintype "bidirectional"))
      (node (ref "U$1") (pin "RED_11") (pinfunction "RED_11_RED_11") (pintype "bidirectional"))
    )
    (net (code "152") (name "/RED_12") (class "Default")
      (node (ref "RED_10") (pin "15") (pinfunction "OUT10_15") (pintype "bidirectional"))
      (node (ref "U$1") (pin "RED_12") (pinfunction "RED_12_RED_12") (pintype "bidirectional"))
    )
    (net (code "153") (name "/RED_13") (class "Default")
      (node (ref "RED_10") (pin "16") (pinfunction "OUT11_16") (pintype "bidirectional"))
      (node (ref "U$1") (pin "RED_13") (pinfunction "RED_13_RED_13") (pintype "bidirectional"))
    )
    (net (code "154") (name "/RED_14") (class "Default")
      (node (ref "RED_10") (pin "17") (pinfunction "OUT12_17") (pintype "bidirectional"))
      (node (ref "U$1") (pin "RED_14") (pinfunction "RED_14_RED_14") (pintype "bidirectional"))
    )
    (net (code "155") (name "/RED_15") (class "Default")
      (node (ref "RED_10") (pin "18") (pinfunction "OUT13_18") (pintype "bidirectional"))
      (node (ref "U$1") (pin "RED_15") (pinfunction "RED_15_RED_15") (pintype "bidirectional"))
    )
    (net (code "156") (name "/RED_16") (class "Default")
      (node (ref "RED_10") (pin "19") (pinfunction "OUT14_19") (pintype "bidirectional"))
      (node (ref "U$1") (pin "RED_16") (pinfunction "RED_16_RED_16") (pintype "bidirectional"))
    )
    (net (code "157") (name "/RED_17") (class "Default")
      (node (ref "RED_10") (pin "20") (pinfunction "OUT15_20") (pintype "bidirectional"))
      (node (ref "U$1") (pin "RED_17") (pinfunction "RED_17_RED_17") (pintype "bidirectional"))
    )
    (net (code "158") (name "/RED_20") (class "Default")
      (node (ref "RED_32") (pin "5") (pinfunction "OUT0_5") (pintype "bidirectional"))
      (node (ref "U$1") (pin "RED_20") (pinfunction "RED_20_RED_20") (pintype "bidirectional"))
    )
    (net (code "159") (name "/RED_21") (class "Default")
      (node (ref "RED_32") (pin "6") (pinfunction "OUT1_6") (pintype "bidirectional"))
      (node (ref "U$1") (pin "RED_21") (pinfunction "RED_21_RED_21") (pintype "bidirectional"))
    )
    (net (code "160") (name "/RED_22") (class "Default")
      (node (ref "RED_32") (pin "7") (pinfunction "OUT2_7") (pintype "bidirectional"))
      (node (ref "U$1") (pin "RED_22") (pinfunction "RED_22_RED_22") (pintype "bidirectional"))
    )
    (net (code "161") (name "/RED_23") (class "Default")
      (node (ref "RED_32") (pin "8") (pinfunction "OUT3_8") (pintype "bidirectional"))
      (node (ref "U$1") (pin "RED_23") (pinfunction "RED_23_RED_23") (pintype "bidirectional"))
    )
    (net (code "162") (name "/RED_24") (class "Default")
      (node (ref "RED_32") (pin "9") (pinfunction "OUT4_9") (pintype "bidirectional"))
      (node (ref "U$1") (pin "RED_24") (pinfunction "RED_24_RED_24") (pintype "bidirectional"))
    )
    (net (code "163") (name "/RED_25") (class "Default")
      (node (ref "RED_32") (pin "10") (pinfunction "OUT5_10") (pintype "bidirectional"))
      (node (ref "U$1") (pin "RED_25") (pinfunction "RED_25_RED_25") (pintype "bidirectional"))
    )
    (net (code "164") (name "/RED_26") (class "Default")
      (node (ref "RED_32") (pin "11") (pinfunction "OUT6_11") (pintype "bidirectional"))
      (node (ref "U$1") (pin "RED_26") (pinfunction "RED_26_RED_26") (pintype "bidirectional"))
    )
    (net (code "165") (name "/RED_27") (class "Default")
      (node (ref "RED_32") (pin "12") (pinfunction "OUT7_12") (pintype "bidirectional"))
      (node (ref "U$1") (pin "RED_27") (pinfunction "RED_27_RED_27") (pintype "bidirectional"))
    )
    (net (code "166") (name "/RED_30") (class "Default")
      (node (ref "RED_32") (pin "13") (pinfunction "OUT8_13") (pintype "bidirectional"))
      (node (ref "U$1") (pin "RED_30") (pinfunction "RED_30_RED_30") (pintype "bidirectional"))
    )
    (net (code "167") (name "/RED_31") (class "Default")
      (node (ref "RED_32") (pin "14") (pinfunction "OUT9_14") (pintype "bidirectional"))
      (node (ref "U$1") (pin "RED_31") (pinfunction "RED_31_RED_31") (pintype "bidirectional"))
    )
    (net (code "168") (name "/RED_32") (class "Default")
      (node (ref "RED_32") (pin "15") (pinfunction "OUT10_15") (pintype "bidirectional"))
      (node (ref "U$1") (pin "RED_32") (pinfunction "RED_32_RED_32") (pintype "bidirectional"))
    )
    (net (code "169") (name "/RED_32_DATA") (class "Default")
      (node (ref "RED_10") (pin "22") (pinfunction "SDO/DAO_22") (pintype "bidirectional"))
      (node (ref "RED_32") (pin "2") (pinfunction "SDI/DAI_2") (pintype "bidirectional"))
    )
    (net (code "170") (name "/RED_33") (class "Default")
      (node (ref "RED_32") (pin "16") (pinfunction "OUT11_16") (pintype "bidirectional"))
      (node (ref "U$1") (pin "RED_33") (pinfunction "RED_33_RED_33") (pintype "bidirectional"))
    )
    (net (code "171") (name "/RED_34") (class "Default")
      (node (ref "RED_32") (pin "17") (pinfunction "OUT12_17") (pintype "bidirectional"))
      (node (ref "U$1") (pin "RED_34") (pinfunction "RED_34_RED_34") (pintype "bidirectional"))
    )
    (net (code "172") (name "/RED_35") (class "Default")
      (node (ref "RED_32") (pin "18") (pinfunction "OUT13_18") (pintype "bidirectional"))
      (node (ref "U$1") (pin "RED_35") (pinfunction "RED_35_RED_35") (pintype "bidirectional"))
    )
    (net (code "173") (name "/RED_36") (class "Default")
      (node (ref "RED_32") (pin "19") (pinfunction "OUT14_19") (pintype "bidirectional"))
      (node (ref "U$1") (pin "RED_36") (pinfunction "RED_36_RED_36") (pintype "bidirectional"))
    )
    (net (code "174") (name "/RED_37") (class "Default")
      (node (ref "RED_32") (pin "20") (pinfunction "OUT15_20") (pintype "bidirectional"))
      (node (ref "U$1") (pin "RED_37") (pinfunction "RED_37_RED_37") (pintype "bidirectional"))
    )
    (net (code "175") (name "/RED_40") (class "Default")
      (node (ref "RED_54") (pin "5") (pinfunction "OUT0_5") (pintype "bidirectional"))
      (node (ref "U$1") (pin "RED_40") (pinfunction "RED_40_RED_40") (pintype "bidirectional"))
    )
    (net (code "176") (name "/RED_41") (class "Default")
      (node (ref "RED_54") (pin "6") (pinfunction "OUT1_6") (pintype "bidirectional"))
      (node (ref "U$1") (pin "RED_41") (pinfunction "RED_41_RED_41") (pintype "bidirectional"))
    )
    (net (code "177") (name "/RED_42") (class "Default")
      (node (ref "RED_54") (pin "7") (pinfunction "OUT2_7") (pintype "bidirectional"))
      (node (ref "U$1") (pin "RED_42") (pinfunction "RED_42_RED_42") (pintype "bidirectional"))
    )
    (net (code "178") (name "/RED_43") (class "Default")
      (node (ref "RED_54") (pin "8") (pinfunction "OUT3_8") (pintype "bidirectional"))
      (node (ref "U$1") (pin "RED_43") (pinfunction "RED_43_RED_43") (pintype "bidirectional"))
    )
    (net (code "179") (name "/RED_44") (class "Default")
      (node (ref "RED_54") (pin "9") (pinfunction "OUT4_9") (pintype "bidirectional"))
      (node (ref "U$1") (pin "RED_44") (pinfunction "RED_44_RED_44") (pintype "bidirectional"))
    )
    (net (code "180") (name "/RED_45") (class "Default")
      (node (ref "RED_54") (pin "10") (pinfunction "OUT5_10") (pintype "bidirectional"))
      (node (ref "U$1") (pin "RED_45") (pinfunction "RED_45_RED_45") (pintype "bidirectional"))
    )
    (net (code "181") (name "/RED_46") (class "Default")
      (node (ref "RED_54") (pin "11") (pinfunction "OUT6_11") (pintype "bidirectional"))
      (node (ref "U$1") (pin "RED_46") (pinfunction "RED_46_RED_46") (pintype "bidirectional"))
    )
    (net (code "182") (name "/RED_47") (class "Default")
      (node (ref "RED_54") (pin "12") (pinfunction "OUT7_12") (pintype "bidirectional"))
      (node (ref "U$1") (pin "RED_47") (pinfunction "RED_47_RED_47") (pintype "bidirectional"))
    )
    (net (code "183") (name "/RED_50") (class "Default")
      (node (ref "RED_54") (pin "13") (pinfunction "OUT8_13") (pintype "bidirectional"))
      (node (ref "U$1") (pin "RED_50") (pinfunction "RED_50_RED_50") (pintype "bidirectional"))
    )
    (net (code "184") (name "/RED_51") (class "Default")
      (node (ref "RED_54") (pin "14") (pinfunction "OUT9_14") (pintype "bidirectional"))
      (node (ref "U$1") (pin "RED_51") (pinfunction "RED_51_RED_51") (pintype "bidirectional"))
    )
    (net (code "185") (name "/RED_52") (class "Default")
      (node (ref "RED_54") (pin "15") (pinfunction "OUT10_15") (pintype "bidirectional"))
      (node (ref "U$1") (pin "RED_52") (pinfunction "RED_52_RED_52") (pintype "bidirectional"))
    )
    (net (code "186") (name "/RED_53") (class "Default")
      (node (ref "RED_54") (pin "16") (pinfunction "OUT11_16") (pintype "bidirectional"))
      (node (ref "U$1") (pin "RED_53") (pinfunction "RED_53_RED_53") (pintype "bidirectional"))
    )
    (net (code "187") (name "/RED_54") (class "Default")
      (node (ref "RED_54") (pin "17") (pinfunction "OUT12_17") (pintype "bidirectional"))
      (node (ref "U$1") (pin "RED_54") (pinfunction "RED_54_RED_54") (pintype "bidirectional"))
    )
    (net (code "188") (name "/RED_54_DATA") (class "Default")
      (node (ref "RED_32") (pin "22") (pinfunction "SDO/DAO_22") (pintype "bidirectional"))
      (node (ref "RED_54") (pin "2") (pinfunction "SDI/DAI_2") (pintype "bidirectional"))
    )
    (net (code "189") (name "/RED_55") (class "Default")
      (node (ref "RED_54") (pin "18") (pinfunction "OUT13_18") (pintype "bidirectional"))
      (node (ref "U$1") (pin "RED_55") (pinfunction "RED_55_RED_55") (pintype "bidirectional"))
    )
    (net (code "190") (name "/RED_56") (class "Default")
      (node (ref "RED_54") (pin "19") (pinfunction "OUT14_19") (pintype "bidirectional"))
      (node (ref "U$1") (pin "RED_56") (pinfunction "RED_56_RED_56") (pintype "bidirectional"))
    )
    (net (code "191") (name "/RED_57") (class "Default")
      (node (ref "RED_54") (pin "20") (pinfunction "OUT15_20") (pintype "bidirectional"))
      (node (ref "U$1") (pin "RED_57") (pinfunction "RED_57_RED_57") (pintype "bidirectional"))
    )
    (net (code "192") (name "/RED_60") (class "Default")
      (node (ref "RED_76") (pin "5") (pinfunction "OUT0_5") (pintype "bidirectional"))
      (node (ref "U$1") (pin "RED_60") (pinfunction "RED_60_RED_60") (pintype "bidirectional"))
    )
    (net (code "193") (name "/RED_61") (class "Default")
      (node (ref "RED_76") (pin "6") (pinfunction "OUT1_6") (pintype "bidirectional"))
      (node (ref "U$1") (pin "RED_61") (pinfunction "RED_61_RED_61") (pintype "bidirectional"))
    )
    (net (code "194") (name "/RED_62") (class "Default")
      (node (ref "RED_76") (pin "7") (pinfunction "OUT2_7") (pintype "bidirectional"))
      (node (ref "U$1") (pin "RED_62") (pinfunction "RED_62_RED_62") (pintype "bidirectional"))
    )
    (net (code "195") (name "/RED_63") (class "Default")
      (node (ref "RED_76") (pin "8") (pinfunction "OUT3_8") (pintype "bidirectional"))
      (node (ref "U$1") (pin "RED_63") (pinfunction "RED_63_RED_63") (pintype "bidirectional"))
    )
    (net (code "196") (name "/RED_64") (class "Default")
      (node (ref "RED_76") (pin "9") (pinfunction "OUT4_9") (pintype "bidirectional"))
      (node (ref "U$1") (pin "RED_64") (pinfunction "RED_64_RED_64") (pintype "bidirectional"))
    )
    (net (code "197") (name "/RED_65") (class "Default")
      (node (ref "RED_76") (pin "10") (pinfunction "OUT5_10") (pintype "bidirectional"))
      (node (ref "U$1") (pin "RED_65") (pinfunction "RED_65_RED_65") (pintype "bidirectional"))
    )
    (net (code "198") (name "/RED_66") (class "Default")
      (node (ref "RED_76") (pin "11") (pinfunction "OUT6_11") (pintype "bidirectional"))
      (node (ref "U$1") (pin "RED_66") (pinfunction "RED_66_RED_66") (pintype "bidirectional"))
    )
    (net (code "199") (name "/RED_67") (class "Default")
      (node (ref "RED_76") (pin "12") (pinfunction "OUT7_12") (pintype "bidirectional"))
      (node (ref "U$1") (pin "RED_67") (pinfunction "RED_67_RED_67") (pintype "bidirectional"))
    )
    (net (code "200") (name "/RED_70") (class "Default")
      (node (ref "RED_76") (pin "13") (pinfunction "OUT8_13") (pintype "bidirectional"))
      (node (ref "U$1") (pin "RED_70") (pinfunction "RED_70_RED_70") (pintype "bidirectional"))
    )
    (net (code "201") (name "/RED_71") (class "Default")
      (node (ref "RED_76") (pin "14") (pinfunction "OUT9_14") (pintype "bidirectional"))
      (node (ref "U$1") (pin "RED_71") (pinfunction "RED_71_RED_71") (pintype "bidirectional"))
    )
    (net (code "202") (name "/RED_72") (class "Default")
      (node (ref "RED_76") (pin "15") (pinfunction "OUT10_15") (pintype "bidirectional"))
      (node (ref "U$1") (pin "RED_72") (pinfunction "RED_72_RED_72") (pintype "bidirectional"))
    )
    (net (code "203") (name "/RED_73") (class "Default")
      (node (ref "RED_76") (pin "16") (pinfunction "OUT11_16") (pintype "bidirectional"))
      (node (ref "U$1") (pin "RED_73") (pinfunction "RED_73_RED_73") (pintype "bidirectional"))
    )
    (net (code "204") (name "/RED_74") (class "Default")
      (node (ref "RED_76") (pin "17") (pinfunction "OUT12_17") (pintype "bidirectional"))
      (node (ref "U$1") (pin "RED_74") (pinfunction "RED_74_RED_74") (pintype "bidirectional"))
    )
    (net (code "205") (name "/RED_75") (class "Default")
      (node (ref "RED_76") (pin "18") (pinfunction "OUT13_18") (pintype "bidirectional"))
      (node (ref "U$1") (pin "RED_75") (pinfunction "RED_75_RED_75") (pintype "bidirectional"))
    )
    (net (code "206") (name "/RED_76") (class "Default")
      (node (ref "RED_76") (pin "19") (pinfunction "OUT14_19") (pintype "bidirectional"))
      (node (ref "U$1") (pin "RED_76") (pinfunction "RED_76_RED_76") (pintype "bidirectional"))
    )
    (net (code "207") (name "/RED_76_DATA") (class "Default")
      (node (ref "RED_54") (pin "22") (pinfunction "SDO/DAO_22") (pintype "bidirectional"))
      (node (ref "RED_76") (pin "2") (pinfunction "SDI/DAI_2") (pintype "bidirectional"))
    )
    (net (code "208") (name "/RED_77") (class "Default")
      (node (ref "RED_76") (pin "20") (pinfunction "OUT15_20") (pintype "bidirectional"))
      (node (ref "U$1") (pin "RED_77") (pinfunction "RED_77_RED_77") (pintype "bidirectional"))
    )
    (net (code "210") (name "GND") (class "Default")
      (node (ref "BLU_10") (pin "1") (pinfunction "GND_1") (pintype "bidirectional"))
      (node (ref "BLU_32") (pin "1") (pinfunction "GND_1") (pintype "bidirectional"))
      (node (ref "BLU_54") (pin "1") (pinfunction "GND_1") (pintype "bidirectional"))
      (node (ref "BLU_76") (pin "1") (pinfunction "GND_1") (pintype "bidirectional"))
      (node (ref "C1") (pin "2") (pinfunction "2_2") (pintype "passive"))
      (node (ref "C10") (pin "2") (pinfunction "2_2") (pintype "passive"))
      (node (ref "C11") (pin "2") (pinfunction "2_2") (pintype "passive"))
      (node (ref "C12") (pin "2") (pinfunction "2_2") (pintype "passive"))
      (node (ref "C2") (pin "2") (pinfunction "2_2") (pintype "passive"))
      (node (ref "C3") (pin "2") (pinfunction "2_2") (pintype "passive"))
      (node (ref "C4") (pin "2") (pinfunction "2_2") (pintype "passive"))
      (node (ref "C5") (pin "2") (pinfunction "2_2") (pintype "passive"))
      (node (ref "C6") (pin "2") (pinfunction "2_2") (pintype "passive"))
      (node (ref "C7") (pin "2") (pinfunction "2_2") (pintype "passive"))
      (node (ref "C8") (pin "2") (pinfunction "2_2") (pintype "passive"))
      (node (ref "C9") (pin "2") (pinfunction "2_2") (pintype "passive"))
      (node (ref "GREEN_10") (pin "1") (pinfunction "GND_1") (pintype "bidirectional"))
      (node (ref "GREEN_32") (pin "1") (pinfunction "GND_1") (pintype "bidirectional"))
      (node (ref "GREEN_54") (pin "1") (pinfunction "GND_1") (pintype "bidirectional"))
      (node (ref "GREEN_76") (pin "1") (pinfunction "GND_1") (pintype "bidirectional"))
      (node (ref "R1") (pin "1") (pinfunction "1_1") (pintype "passive"))
      (node (ref "R10") (pin "1") (pinfunction "1_1") (pintype "passive"))
      (node (ref "R11") (pin "1") (pinfunction "1_1") (pintype "passive"))
      (node (ref "R12") (pin "1") (pinfunction "1_1") (pintype "passive"))
      (node (ref "R2") (pin "1") (pinfunction "1_1") (pintype "passive"))
      (node (ref "R3") (pin "1") (pinfunction "1_1") (pintype "passive"))
      (node (ref "R4") (pin "1") (pinfunction "1_1") (pintype "passive"))
      (node (ref "R5") (pin "1") (pinfunction "1_1") (pintype "passive"))
      (node (ref "R6") (pin "1") (pinfunction "1_1") (pintype "passive"))
      (node (ref "R7") (pin "1") (pinfunction "1_1") (pintype "passive"))
      (node (ref "R8") (pin "1") (pinfunction "1_1") (pintype "passive"))
      (node (ref "R9") (pin "1") (pinfunction "1_1") (pintype "passive"))
      (node (ref "RED_10") (pin "1") (pinfunction "GND_1") (pintype "bidirectional"))
      (node (ref "RED_32") (pin "1") (pinfunction "GND_1") (pintype "bidirectional"))
      (node (ref "RED_54") (pin "1") (pinfunction "GND_1") (pintype "bidirectional"))
      (node (ref "RED_76") (pin "1") (pinfunction "GND_1") (pintype "bidirectional"))
      (node (ref "SV1") (pin "1") (pinfunction "1_1") (pintype "passive"))
      (node (ref "SV1") (pin "2") (pinfunction "2_2") (pintype "passive"))
    )
    (net (code "211") (name "Net-(BLU_10-REXT)") (class "Default")
      (node (ref "BLU_10") (pin "23") (pinfunction "REXT_23") (pintype "bidirectional"))
      (node (ref "R9") (pin "2") (pinfunction "2_2") (pintype "passive"))
    )
    (net (code "212") (name "Net-(BLU_32-REXT)") (class "Default")
      (node (ref "BLU_32") (pin "23") (pinfunction "REXT_23") (pintype "bidirectional"))
      (node (ref "R10") (pin "2") (pinfunction "2_2") (pintype "passive"))
    )
    (net (code "213") (name "Net-(BLU_54-REXT)") (class "Default")
      (node (ref "BLU_54") (pin "23") (pinfunction "REXT_23") (pintype "bidirectional"))
      (node (ref "R11") (pin "2") (pinfunction "2_2") (pintype "passive"))
    )
    (net (code "214") (name "Net-(BLU_76-REXT)") (class "Default")
      (node (ref "BLU_76") (pin "23") (pinfunction "REXT_23") (pintype "bidirectional"))
      (node (ref "R12") (pin "2") (pinfunction "2_2") (pintype "passive"))
    )
    (net (code "215") (name "Net-(GREEN_10-REXT)") (class "Default")
      (node (ref "GREEN_10") (pin "23") (pinfunction "REXT_23") (pintype "bidirectional"))
      (node (ref "R5") (pin "2") (pinfunction "2_2") (pintype "passive"))
    )
    (net (code "216") (name "Net-(GREEN_32-REXT)") (class "Default")
      (node (ref "GREEN_32") (pin "23") (pinfunction "REXT_23") (pintype "bidirectional"))
      (node (ref "R6") (pin "2") (pinfunction "2_2") (pintype "passive"))
    )
    (net (code "217") (name "Net-(GREEN_54-REXT)") (class "Default")
      (node (ref "GREEN_54") (pin "23") (pinfunction "REXT_23") (pintype "bidirectional"))
      (node (ref "R7") (pin "2") (pinfunction "2_2") (pintype "passive"))
    )
    (net (code "218") (name "Net-(GREEN_76-REXT)") (class "Default")
      (node (ref "GREEN_76") (pin "23") (pinfunction "REXT_23") (pintype "bidirectional"))
      (node (ref "R8") (pin "2") (pinfunction "2_2") (pintype "passive"))
    )
    (net (code "219") (name "Net-(RED_10-REXT)") (class "Default")
      (node (ref "R1") (pin "2") (pinfunction "2_2") (pintype "passive"))
      (node (ref "RED_10") (pin "23") (pinfunction "REXT_23") (pintype "bidirectional"))
    )
    (net (code "220") (name "Net-(RED_32-REXT)") (class "Default")
      (node (ref "R2") (pin "2") (pinfunction "2_2") (pintype "passive"))
      (node (ref "RED_32") (pin "23") (pinfunction "REXT_23") (pintype "bidirectional"))
    )
    (net (code "221") (name "Net-(RED_54-REXT)") (class "Default")
      (node (ref "R3") (pin "2") (pinfunction "2_2") (pintype "passive"))
      (node (ref "RED_54") (pin "23") (pinfunction "REXT_23") (pintype "bidirectional"))
    )
    (net (code "222") (name "Net-(RED_76-REXT)") (class "Default")
      (node (ref "R4") (pin "2") (pinfunction "2_2") (pintype "passive"))
      (node (ref "RED_76") (pin "23") (pinfunction "REXT_23") (pintype "bidirectional"))
    )
    (net (code "223") (name "VCC") (class "Default")
      (node (ref "BLU_10") (pin "24") (pinfunction "VDD_24") (pintype "bidirectional"))
      (node (ref "BLU_32") (pin "24") (pinfunction "VDD_24") (pintype "bidirectional"))
      (node (ref "BLU_54") (pin "24") (pinfunction "VDD_24") (pintype "bidirectional"))
      (node (ref "BLU_76") (pin "24") (pinfunction "VDD_24") (pintype "bidirectional"))
      (node (ref "C1") (pin "1") (pinfunction "1_1") (pintype "passive"))
      (node (ref "C10") (pin "1") (pinfunction "1_1") (pintype "passive"))
      (node (ref "C11") (pin "1") (pinfunction "1_1") (pintype "passive"))
      (node (ref "C12") (pin "1") (pinfunction "1_1") (pintype "passive"))
      (node (ref "C2") (pin "1") (pinfunction "1_1") (pintype "passive"))
      (node (ref "C3") (pin "1") (pinfunction "1_1") (pintype "passive"))
      (node (ref "C4") (pin "1") (pinfunction "1_1") (pintype "passive"))
      (node (ref "C5") (pin "1") (pinfunction "1_1") (pintype "passive"))
      (node (ref "C6") (pin "1") (pinfunction "1_1") (pintype "passive"))
      (node (ref "C7") (pin "1") (pinfunction "1_1") (pintype "passive"))
      (node (ref "C8") (pin "1") (pinfunction "1_1") (pintype "passive"))
      (node (ref "C9") (pin "1") (pinfunction "1_1") (pintype "passive"))
      (node (ref "GREEN_10") (pin "24") (pinfunction "VDD_24") (pintype "bidirectional"))
      (node (ref "GREEN_32") (pin "24") (pinfunction "VDD_24") (pintype "bidirectional"))
      (node (ref "GREEN_54") (pin "24") (pinfunction "VDD_24") (pintype "bidirectional"))
      (node (ref "GREEN_76") (pin "24") (pinfunction "VDD_24") (pintype "bidirectional"))
      (node (ref "RED_10") (pin "24") (pinfunction "VDD_24") (pintype "bidirectional"))
      (node (ref "RED_32") (pin "24") (pinfunction "VDD_24") (pintype "bidirectional"))
      (node (ref "RED_54") (pin "24") (pinfunction "VDD_24") (pintype "bidirectional"))
      (node (ref "RED_76") (pin "24") (pinfunction "VDD_24") (pintype "bidirectional"))
      (node (ref "SV1") (pin "12") (pinfunction "12_12") (pintype "passive"))
    )
    (net (code "224") (name "unconnected-(RED_76-SDO{slash}DAO-Pad22)") (class "Default")
      (node (ref "RED_76") (pin "22") (pinfunction "SDO/DAO_22") (pintype "bidirectional"))
    )
    (net (code "225") (name "unconnected-(SV1-Pad7)") (class "Default")
      (node (ref "SV1") (pin "7") (pinfunction "7_7") (pintype "passive"))
    )
    (net (code "226") (name "unconnected-(SV1-Pad8)") (class "Default")
      (node (ref "SV1") (pin "8") (pinfunction "8_8") (pintype "passive"))
    )
    (net (code "227") (name "unconnected-(SV1-Pad9)") (class "Default")
      (node (ref "SV1") (pin "9") (pinfunction "9_9") (pintype "passive"))
    )
    (net (code "228") (name "unconnected-(SV1-Pad10)") (class "Default")
      (node (ref "SV1") (pin "10") (pinfunction "10_10") (pintype "passive"))
    )
    (net (code "229") (name "unconnected-(SV1-Pad11)") (class "Default")
      (node (ref "SV1") (pin "11") (pinfunction "11_11") (pintype "passive"))
    )
    (net (code "230") (name "unconnected-(SV2-Pad1)") (class "Default")
      (node (ref "SV2") (pin "1") (pinfunction "1_1") (pintype "passive"))
    )
    (net (code "231") (name "unconnected-(SV2-Pad2)") (class "Default")
      (node (ref "SV2") (pin "2") (pinfunction "2_2") (pintype "passive"))
    )
    (net (code "232") (name "unconnected-(SV2-Pad3)") (class "Default")
      (node (ref "SV2") (pin "3") (pinfunction "3_3") (pintype "passive"))
    )
    (net (code "233") (name "unconnected-(SV2-Pad4)") (class "Default")
      (node (ref "SV2") (pin "4") (pinfunction "4_4") (pintype "passive"))
    )
    (net (code "234") (name "unconnected-(SV2-Pad5)") (class "Default")
      (node (ref "SV2") (pin "5") (pinfunction "5_5") (pintype "passive"))
    )
    (net (code "235") (name "unconnected-(SV2-Pad6)") (class "Default")
      (node (ref "SV2") (pin "6") (pinfunction "6_6") (pintype "passive"))
    )
    (net (code "236") (name "unconnected-(SV2-Pad7)") (class "Default")
      (node (ref "SV2") (pin "7") (pinfunction "7_7") (pintype "passive"))
    )
    (net (code "237") (name "unconnected-(SV2-Pad8)") (class "Default")
      (node (ref "SV2") (pin "8") (pinfunction "8_8") (pintype "passive"))
    )
  )
)
